# Backplane_Breakout_Adapter_Pico.net
KiCad netlist of a schematic drawn in Altium Designer
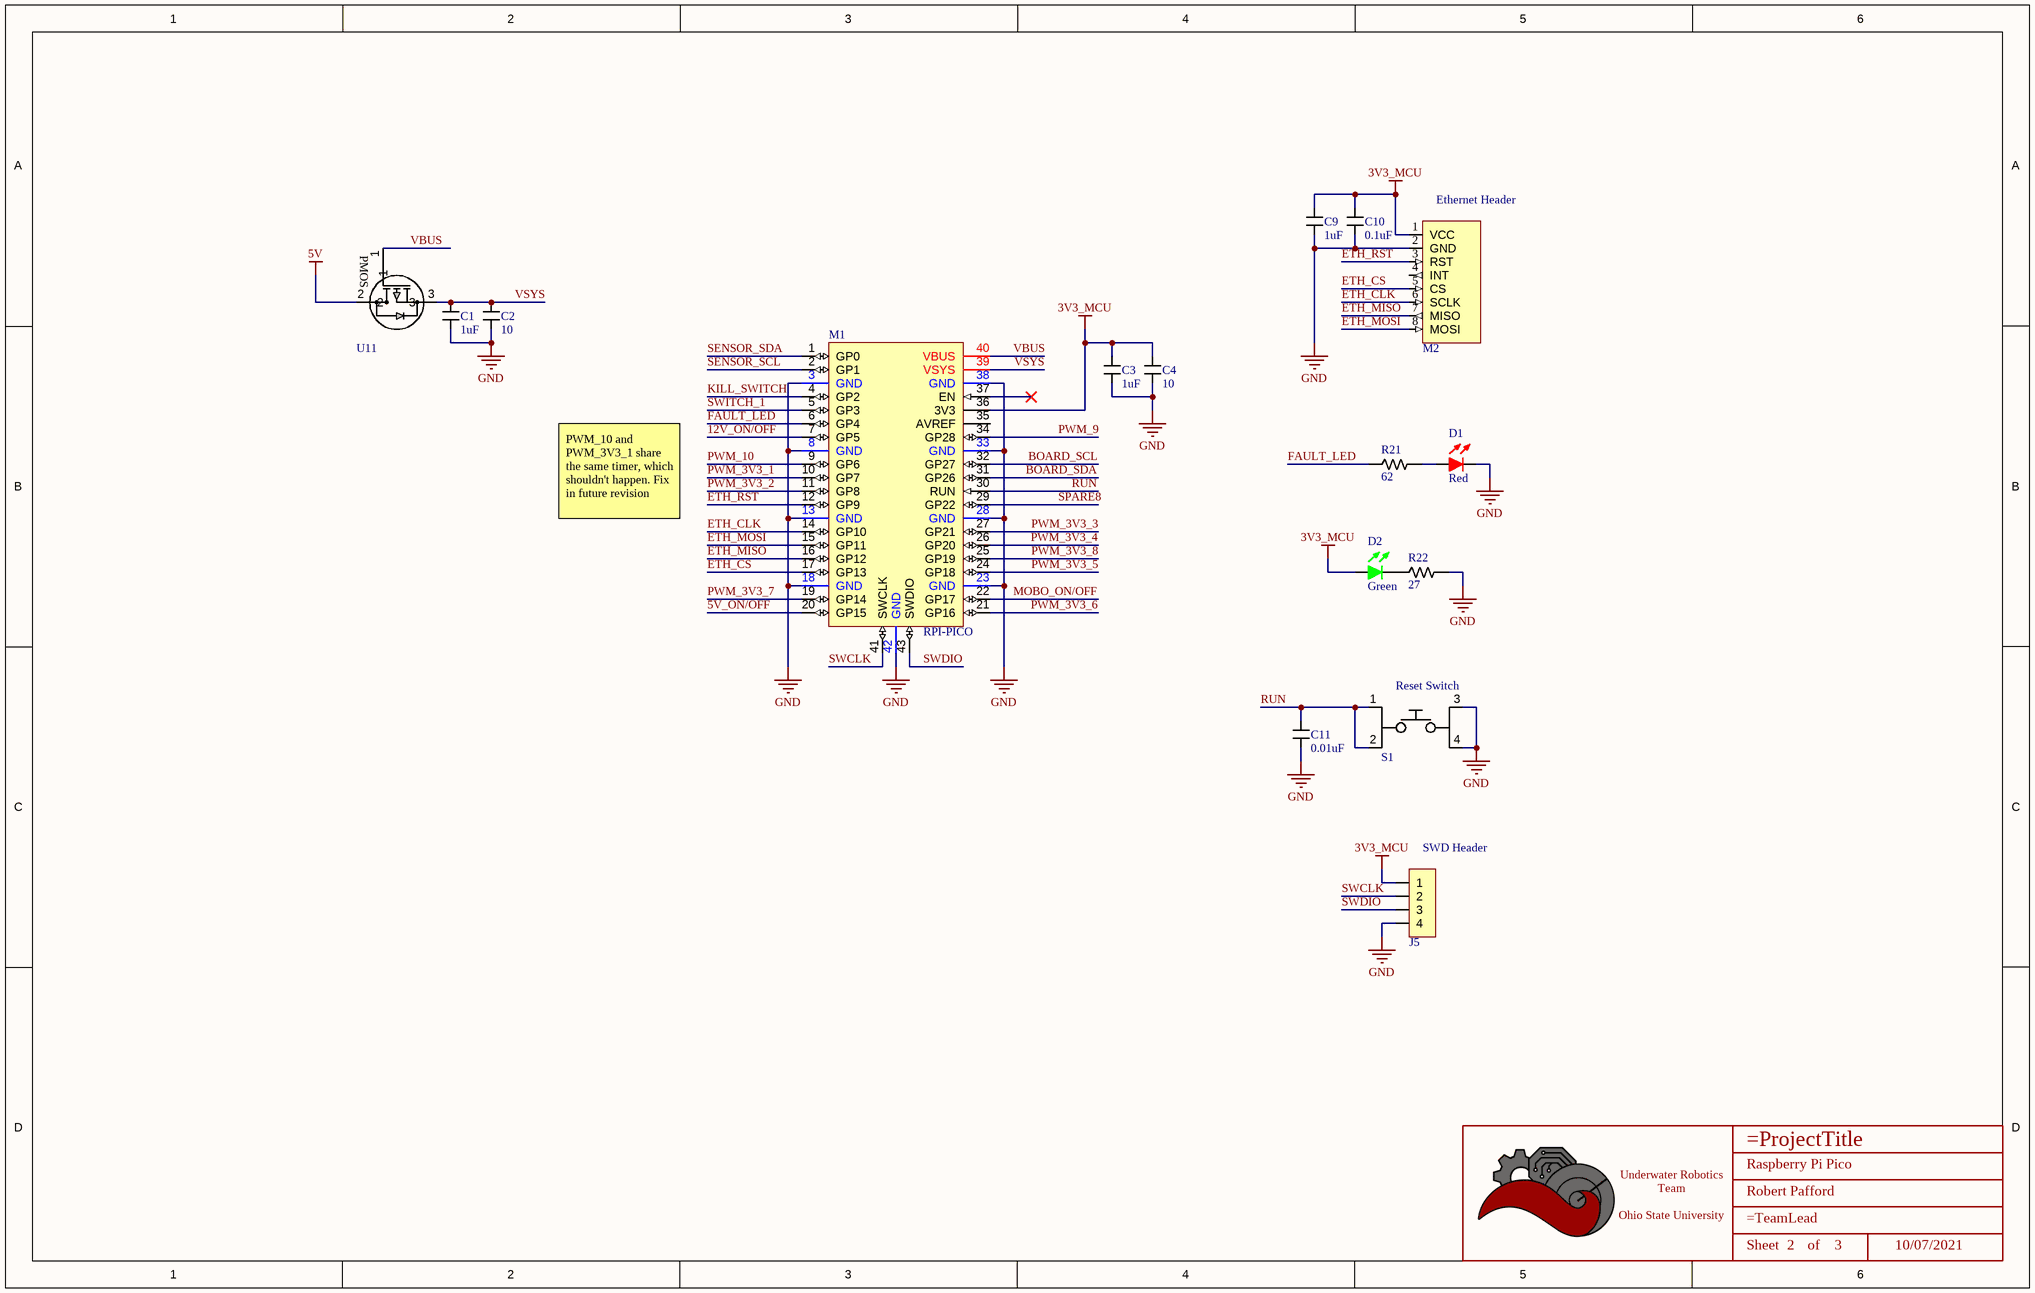
[diagram p0: Backplane_Breakout_Adapter_Pico.SchDoc]

(export (version "E")
  (design (tool "Eeschema 10.0.6"))
  (components
    (comp (ref "*")
      (value "Title_Block")
      (footprint "LOGO")
      (description "UWRT Schematic Title Block Template\r\n\r\nCreated June 2021, Dylan Trainor")
      (libsource (lib "UWRT") (part "Title_Block"))
    )
    (comp (ref "C1")
      (value "1uF")
      (footprint "CAPACITOR_0603")
      (description "Cap 1uF 16V +/-10%\r\nCeramic 0603")
      (fields
        (field (name "TOLERANCE") "+/- 10%")
        (field (name "VOLTAGE") "16V")
        (field (name "MADE BY") "Flip B")
      )
      (libsource (lib "Capacitors") (part "CAPACITOR_1uF_0603"))
    )
    (comp (ref "C2")
      (value "10uF Ceramic 6.3V")
      (footprint "CAPACITOR_0603")
      (description "Cap 10uF 6.3V +/-20%\r\nCeramic 0603")
      (fields
        (field (name "TOLERANCE") "+/- 20%")
        (field (name "VOLTAGE") "6.3V")
        (field (name "VALUE (UF)") "10")
        (field (name "MADE BY") "Flip B")
      )
      (libsource (lib "Capacitors") (part "CAPACITOR_10uF_0603"))
    )
    (comp (ref "C3")
      (value "1uF")
      (footprint "CAPACITOR_0603")
      (description "Cap 1uF 16V +/-10%\r\nCeramic 0603")
      (fields
        (field (name "TOLERANCE") "+/- 10%")
        (field (name "VOLTAGE") "16V")
        (field (name "MADE BY") "Flip B")
      )
      (libsource (lib "Capacitors") (part "CAPACITOR_1uF_0603"))
    )
    (comp (ref "C4")
      (value "10uF Ceramic 6.3V")
      (footprint "CAPACITOR_0603")
      (description "Cap 10uF 6.3V +/-20%\r\nCeramic 0603")
      (fields
        (field (name "TOLERANCE") "+/- 20%")
        (field (name "VOLTAGE") "6.3V")
        (field (name "VALUE (UF)") "10")
        (field (name "MADE BY") "Flip B")
      )
      (libsource (lib "Capacitors") (part "CAPACITOR_10uF_0603"))
    )
    (comp (ref "C9")
      (value "1uF")
      (footprint "CAPACITOR_0603")
      (description "Cap 1uF 16V +/-10%\r\nCeramic 0603")
      (fields
        (field (name "TOLERANCE") "+/- 10%")
        (field (name "VOLTAGE") "16V")
        (field (name "MADE BY") "Flip B")
      )
      (libsource (lib "Capacitors") (part "CAPACITOR_1uF_0603"))
    )
    (comp (ref "C10")
      (value "0.1uF")
      (footprint "CAPACITOR_0603")
      (description "Cap 100nF 6.3V +/-10%\r\nCeramic 0603")
      (fields
        (field (name "TOLERANCE") "+/- 10%")
        (field (name "VOLTAGE") "6.3V")
        (field (name "MADE BY") "Flip B")
      )
      (libsource (lib "Capacitors") (part "CAPACITOR_0.1uF_0603"))
    )
    (comp (ref "C11")
      (value "0.01uF")
      (footprint "CAPACITOR_0603")
      (description "Cap 10nF 6.3V +/-20%\r\nCeramic 0603")
      (fields
        (field (name "TOLERANCE") "+/- 10%")
        (field (name "VOLTAGE") "6.3V")
        (field (name "MADE BY") "Flip B")
      )
      (libsource (lib "Capacitors") (part "CAPACITOR_0.01uF_0603"))
    )
    (comp (ref "D1")
      (value "150060RS75000")
      (footprint "LED_0603")
      (description "LED Red Vf= 2V If = 0.020A\r\nIN-S63AT5G")
      (fields (field (name "COLOR") "Red") (field (name "MADE BY") "Robert Pafford"))
      (libsource (lib "Diodes") (part "LED_Red_0603"))
    )
    (comp (ref "D2")
      (value "150060GS75000")
      (footprint "LED_0603")
      (description "LED Green Vf= 3.2V If = 0.025A\r\n150060GS75000")
      (fields (field (name "COLOR") "Green") (field (name "MADE BY") "Flip B"))
      (libsource (lib "Diodes") (part "LED_Green_0603_3.2V"))
    )
    (comp (ref "J5")
      (value "CONN HEADER VERT 4POS 2.54MM")
      (footprint "HEADER_4PIN_2.54MM")
      (fields (field (name "MADE BY") "Robert Pafford"))
      (libsource (lib "Connectors") (part "HEADER_4PIN_2.54MM"))
    )
    (comp (ref "M1")
      (value "RPI-PICO")
      (footprint "Modules:RPI-PICO-MOD")
      (description "RASPBERRY PI PICO RP2040 BOARD NO TEST PADS")
      (fields
        (field (name "MANUFACTURER") "Raspberry Pi Foundation")
        (field (name "MANUFACTURER PART NO") "SC0915")
      )
      (libsource (lib "Modules") (part "RPI-PICO-MOD_SM"))
    )
    (comp (ref "M2")
      (value "W5x00 Breakout Board")
      (footprint "W5500IO-P")
      (description "W5x00 Breakout Board (W5500IO-P Compatible boards)")
      (fields (field (name "VOLTAGE") "3.3V") (field (name "MADE BY") "Robert Pafford"))
      (libsource (lib "Modules") (part "W5500IO-P"))
    )
    (comp (ref "R21")
      (value "62 Ohm 1% 1/4W")
      (footprint "RESISTOR_0603")
      (description "RES SMD 62 OHM 1% 1/4W 0603")
      (fields
        (field (name "TOLERANCE") "+/- 1%")
        (field (name "VALUE  (OHMS)") "62")
        (field (name "MADE BY") "Robert Pafford")
      )
      (libsource (lib "Resistors") (part "RESISTOR_62_0603"))
    )
    (comp (ref "R22")
      (value "27 Ohm 5% 1/8W")
      (footprint "RESISTOR_0603")
      (description "RES 27 OHM 5% 1/8W 0603")
      (fields
        (field (name "TOLERANCE") "+/- 5%")
        (field (name "VALUE  (OHMS)") "27")
        (field (name "MADE BY") "Robert Pafford")
      )
      (libsource (lib "Resistors") (part "RESISTOR_27_0603"))
    )
    (comp (ref "S1")
      (value "SPST Tactile Switch")
      (footprint "TactileSwitch")
      (description "SWITCH TACTILE SPST-NO 0.05A 12V")
      (fields (field (name "MADE BY") "Robert Pafford"))
      (libsource (lib "Switches") (part "Tactile Switch"))
    )
    (comp (ref "U11")
      (value "MOSFET P-CHANNEL 20V 4.7A SOT23")
      (footprint "SOT-23-3")
      (description "P-Channel 20 V 4.7A (Tc) 1.56W (Tc) Surface Mount SOT-23")
      (fields
        (field (name "MANUFACTURER_PART_NUMBER") "TSM500P02CX")
        (field (name "CREATED BY") "Robert Pafford")
      )
      (libsource (lib "Transistors") (part "TSM500P02CX"))
    )
  )
  (nets
    (net (code "1") (name "/5V_ON{slash}OFF") (class "Default")
      (node (ref "M1") (pin "20") (pinfunction "GP15_20") (pintype "bidirectional"))
    )
    (net (code "2") (name "/12V_ON{slash}OFF") (class "Default")
      (node (ref "M1") (pin "7") (pinfunction "GP5_7") (pintype "bidirectional"))
    )
    (net (code "3") (name "/BOARD_SCL") (class "Default")
      (node (ref "M1") (pin "32") (pinfunction "GP27_32") (pintype "bidirectional"))
    )
    (net (code "4") (name "/BOARD_SDA") (class "Default")
      (node (ref "M1") (pin "31") (pinfunction "GP26_31") (pintype "bidirectional"))
    )
    (net (code "5") (name "/ETH_CLK") (class "Default")
      (node (ref "M1") (pin "14") (pinfunction "GP10_14") (pintype "bidirectional"))
      (node (ref "M2") (pin "6") (pinfunction "SCLK_6") (pintype "input"))
    )
    (net (code "6") (name "/ETH_CS") (class "Default")
      (node (ref "M1") (pin "17") (pinfunction "GP13_17") (pintype "bidirectional"))
      (node (ref "M2") (pin "5") (pinfunction "CS_5") (pintype "input"))
    )
    (net (code "7") (name "/ETH_MISO") (class "Default")
      (node (ref "M1") (pin "16") (pinfunction "GP12_16") (pintype "bidirectional"))
      (node (ref "M2") (pin "7") (pinfunction "MISO_7") (pintype "output"))
    )
    (net (code "8") (name "/ETH_MOSI") (class "Default")
      (node (ref "M1") (pin "15") (pinfunction "GP11_15") (pintype "bidirectional"))
      (node (ref "M2") (pin "8") (pinfunction "MOSI_8") (pintype "input"))
    )
    (net (code "9") (name "/ETH_RST") (class "Default")
      (node (ref "M1") (pin "12") (pinfunction "GP9_12") (pintype "bidirectional"))
      (node (ref "M2") (pin "3") (pinfunction "RST_3") (pintype "input"))
    )
    (net (code "10") (name "/FAULT_LED") (class "Default")
      (node (ref "M1") (pin "6") (pinfunction "GP4_6") (pintype "bidirectional"))
      (node (ref "R21") (pin "2") (pinfunction "2_2") (pintype "passive"))
    )
    (net (code "11") (name "/KILL_SWITCH") (class "Default")
      (node (ref "M1") (pin "4") (pinfunction "GP2_4") (pintype "bidirectional"))
    )
    (net (code "12") (name "/MOBO_ON{slash}OFF") (class "Default")
      (node (ref "M1") (pin "22") (pinfunction "GP17_22") (pintype "bidirectional"))
    )
    (net (code "13") (name "/PWM_3V3_1") (class "Default")
      (node (ref "M1") (pin "10") (pinfunction "GP7_10") (pintype "bidirectional"))
    )
    (net (code "14") (name "/PWM_3V3_2") (class "Default")
      (node (ref "M1") (pin "11") (pinfunction "GP8_11") (pintype "bidirectional"))
    )
    (net (code "15") (name "/PWM_3V3_3") (class "Default")
      (node (ref "M1") (pin "27") (pinfunction "GP21_27") (pintype "bidirectional"))
    )
    (net (code "16") (name "/PWM_3V3_4") (class "Default")
      (node (ref "M1") (pin "26") (pinfunction "GP20_26") (pintype "bidirectional"))
    )
    (net (code "17") (name "/PWM_3V3_5") (class "Default")
      (node (ref "M1") (pin "24") (pinfunction "GP18_24") (pintype "bidirectional"))
    )
    (net (code "18") (name "/PWM_3V3_6") (class "Default")
      (node (ref "M1") (pin "21") (pinfunction "GP16_21") (pintype "bidirectional"))
    )
    (net (code "19") (name "/PWM_3V3_7") (class "Default")
      (node (ref "M1") (pin "19") (pinfunction "GP14_19") (pintype "bidirectional"))
    )
    (net (code "20") (name "/PWM_3V3_8") (class "Default")
      (node (ref "M1") (pin "25") (pinfunction "GP19_25") (pintype "bidirectional"))
    )
    (net (code "21") (name "/PWM_9") (class "Default")
      (node (ref "M1") (pin "34") (pinfunction "GP28_34") (pintype "bidirectional"))
    )
    (net (code "22") (name "/PWM_10") (class "Default")
      (node (ref "M1") (pin "9") (pinfunction "GP6_9") (pintype "bidirectional"))
    )
    (net (code "23") (name "/RUN") (class "Default")
      (node (ref "C11") (pin "1") (pinfunction "1_1") (pintype "passive"))
      (node (ref "M1") (pin "30") (pinfunction "RUN_30") (pintype "input"))
      (node (ref "S1") (pin "1") (pinfunction "1_1") (pintype "passive"))
      (node (ref "S1") (pin "2") (pinfunction "2_2") (pintype "passive"))
    )
    (net (code "24") (name "/SENSOR_SCL") (class "Default")
      (node (ref "M1") (pin "2") (pinfunction "GP1_2") (pintype "bidirectional"))
    )
    (net (code "25") (name "/SENSOR_SDA") (class "Default")
      (node (ref "M1") (pin "1") (pinfunction "GP0_1") (pintype "bidirectional"))
    )
    (net (code "26") (name "/SPARE8") (class "Default")
      (node (ref "M1") (pin "29") (pinfunction "GP22_29") (pintype "bidirectional"))
    )
    (net (code "27") (name "/SWCLK") (class "Default")
      (node (ref "J5") (pin "2") (pinfunction "2_2") (pintype "passive"))
      (node (ref "M1") (pin "41") (pinfunction "SWCLK_41") (pintype "bidirectional"))
    )
    (net (code "28") (name "/SWDIO") (class "Default")
      (node (ref "J5") (pin "3") (pinfunction "3_3") (pintype "passive"))
      (node (ref "M1") (pin "43") (pinfunction "SWDIO_43") (pintype "bidirectional"))
    )
    (net (code "29") (name "/SWITCH_1") (class "Default")
      (node (ref "M1") (pin "5") (pinfunction "GP3_5") (pintype "bidirectional"))
    )
    (net (code "30") (name "/VBUS") (class "Default")
      (node (ref "M1") (pin "40") (pinfunction "VBUS_40") (pintype "power_in"))
      (node (ref "U11") (pin "1") (pinfunction "1_1") (pintype "passive"))
    )
    (net (code "31") (name "/VSYS") (class "Default")
      (node (ref "C1") (pin "1") (pinfunction "1_1") (pintype "passive"))
      (node (ref "C2") (pin "1") (pinfunction "1_1") (pintype "passive"))
      (node (ref "M1") (pin "39") (pinfunction "VSYS_39") (pintype "power_in"))
      (node (ref "U11") (pin "3") (pinfunction "3_3") (pintype "passive"))
    )
    (net (code "32") (name "3V3_MCU") (class "Default")
      (node (ref "C10") (pin "1") (pinfunction "1_1") (pintype "passive"))
      (node (ref "C3") (pin "1") (pinfunction "1_1") (pintype "passive"))
      (node (ref "C4") (pin "1") (pinfunction "1_1") (pintype "passive"))
      (node (ref "C9") (pin "1") (pinfunction "1_1") (pintype "passive"))
      (node (ref "D2") (pin "1") (pinfunction "1_1") (pintype "passive"))
      (node (ref "J5") (pin "1") (pinfunction "1_1") (pintype "passive"))
      (node (ref "M1") (pin "36") (pinfunction "3V3_36") (pintype "power_in"))
      (node (ref "M2") (pin "1") (pinfunction "VCC_1") (pintype "power_in"))
    )
    (net (code "33") (name "5V") (class "Default")
      (node (ref "U11") (pin "2") (pinfunction "2_2") (pintype "passive"))
    )
    (net (code "34") (name "GND") (class "Default")
      (node (ref "C1") (pin "2") (pinfunction "2_2") (pintype "passive"))
      (node (ref "C10") (pin "2") (pinfunction "2_2") (pintype "passive"))
      (node (ref "C11") (pin "2") (pinfunction "2_2") (pintype "passive"))
      (node (ref "C2") (pin "2") (pinfunction "2_2") (pintype "passive"))
      (node (ref "C3") (pin "2") (pinfunction "2_2") (pintype "passive"))
      (node (ref "C4") (pin "2") (pinfunction "2_2") (pintype "passive"))
      (node (ref "C9") (pin "2") (pinfunction "2_2") (pintype "passive"))
      (node (ref "D1") (pin "2") (pinfunction "2_2") (pintype "passive"))
      (node (ref "J5") (pin "4") (pinfunction "4_4") (pintype "passive"))
      (node (ref "M1") (pin "13") (pinfunction "GND_13") (pintype "power_in"))
      (node (ref "M1") (pin "18") (pinfunction "GND_18") (pintype "power_in"))
      (node (ref "M1") (pin "23") (pinfunction "GND_23") (pintype "power_in"))
      (node (ref "M1") (pin "28") (pinfunction "GND_28") (pintype "power_in"))
      (node (ref "M1") (pin "3") (pinfunction "GND_3") (pintype "power_in"))
      (node (ref "M1") (pin "33") (pinfunction "GND_33") (pintype "power_in"))
      (node (ref "M1") (pin "38") (pinfunction "GND_38") (pintype "power_in"))
      (node (ref "M1") (pin "42") (pinfunction "GND_42") (pintype "power_in"))
      (node (ref "M1") (pin "8") (pinfunction "GND_8") (pintype "power_in"))
      (node (ref "M2") (pin "2") (pinfunction "GND_2") (pintype "power_in"))
      (node (ref "R22") (pin "1") (pinfunction "1_1") (pintype "passive"))
      (node (ref "S1") (pin "3") (pinfunction "3_3") (pintype "passive"))
      (node (ref "S1") (pin "4") (pinfunction "4_4") (pintype "passive"))
    )
    (net (code "35") (name "Net-(D1-Pad1)") (class "Default")
      (node (ref "D1") (pin "1") (pinfunction "1_1") (pintype "passive"))
      (node (ref "R21") (pin "1") (pinfunction "1_1") (pintype "passive"))
    )
    (net (code "36") (name "Net-(D2-Pad2)") (class "Default")
      (node (ref "D2") (pin "2") (pinfunction "2_2") (pintype "passive"))
      (node (ref "R22") (pin "2") (pinfunction "2_2") (pintype "passive"))
    )
    (net (code "37") (name "unconnected-(M1-AVREF-Pad35)") (class "Default")
      (node (ref "M1") (pin "35") (pinfunction "AVREF_35") (pintype "power_in"))
    )
    (net (code "38") (name "unconnected-(M1-EN-Pad37)") (class "Default")
      (node (ref "M1") (pin "37") (pinfunction "EN_37") (pintype "input+no_connect"))
    )
    (net (code "39") (name "unconnected-(M2-INT-Pad4)") (class "Default")
      (node (ref "M2") (pin "4") (pinfunction "INT_4") (pintype "output"))
    )
  )
)
